# prm_405.net
KiCad netlist of a schematic drawn in EAGLE
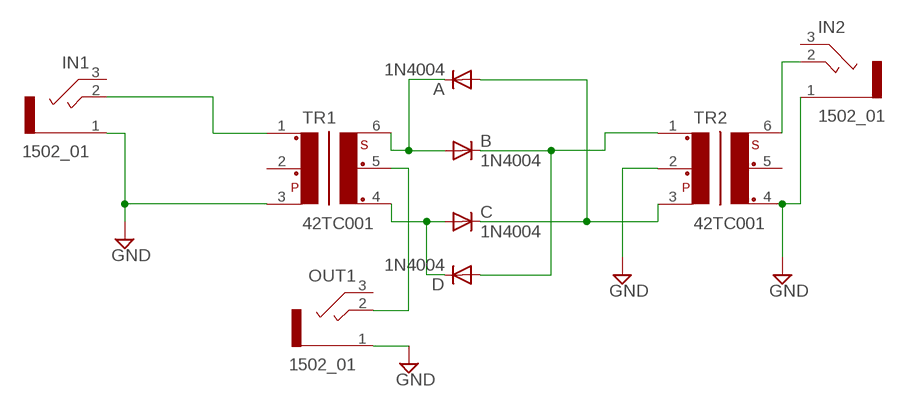
[diagram p0: schematic, sheet 1]

(export (version "E")
  (design (tool "Eeschema 10.0.6"))
  (components
    (comp (ref "A")
      (value "1N4004")
      (footprint "eagle-import:DO41-10")
      (libsource (lib "eagle-import") (part "1N4004"))
    )
    (comp (ref "B")
      (value "1N4004")
      (footprint "eagle-import:DO41-10")
      (libsource (lib "eagle-import") (part "1N4004"))
    )
    (comp (ref "C")
      (value "1N4004")
      (footprint "eagle-import:DO41-10")
      (libsource (lib "eagle-import") (part "1N4004"))
    )
    (comp (ref "D")
      (value "1N4004")
      (footprint "eagle-import:DO41-10")
      (libsource (lib "eagle-import") (part "1N4004"))
    )
    (comp (ref "IN1")
      (value "1502_01")
      (footprint "eagle-import:1502_01")
      (libsource (lib "eagle-import") (part "1502_01"))
    )
    (comp (ref "IN2")
      (value "1502_01")
      (footprint "eagle-import:1502_01")
      (libsource (lib "eagle-import") (part "1502_01"))
    )
    (comp (ref "OUT1")
      (value "1502_01")
      (footprint "eagle-import:1502_01")
      (libsource (lib "eagle-import") (part "1502_01"))
    )
    (comp (ref "TR1")
      (value "42TC001")
      (footprint "eagle-import:42TC")
      (libsource (lib "eagle-import") (part "42T?C001"))
    )
    (comp (ref "TR2")
      (value "42TC001")
      (footprint "eagle-import:42TC")
      (libsource (lib "eagle-import") (part "42T?C001"))
    )
  )
  (nets
    (net (code "1") (name "GND") (class "Default")
      (node (ref "IN1") (pin "1") (pinfunction "1_1") (pintype "passive"))
      (node (ref "IN2") (pin "1") (pinfunction "1_1") (pintype "passive"))
      (node (ref "OUT1") (pin "1") (pinfunction "1_1") (pintype "passive"))
      (node (ref "TR1") (pin "3") (pinfunction "3_3") (pintype "passive"))
      (node (ref "TR2") (pin "2") (pinfunction "2_2") (pintype "passive"))
      (node (ref "TR2") (pin "4") (pinfunction "4_4") (pintype "passive"))
    )
    (net (code "2") (name "Net-(A-PadA)") (class "Default")
      (node (ref "A") (pin "A") (pinfunction "A_A") (pintype "passive"))
      (node (ref "C") (pin "C") (pinfunction "C_C") (pintype "passive"))
      (node (ref "TR2") (pin "3") (pinfunction "3_3") (pintype "passive"))
    )
    (net (code "3") (name "Net-(A-PadC)") (class "Default")
      (node (ref "A") (pin "C") (pinfunction "C_C") (pintype "passive"))
      (node (ref "B") (pin "A") (pinfunction "A_A") (pintype "passive"))
      (node (ref "TR1") (pin "6") (pinfunction "6_6") (pintype "passive"))
    )
    (net (code "4") (name "Net-(B-PadC)") (class "Default")
      (node (ref "B") (pin "C") (pinfunction "C_C") (pintype "passive"))
      (node (ref "D") (pin "A") (pinfunction "A_A") (pintype "passive"))
      (node (ref "TR2") (pin "1") (pinfunction "1_1") (pintype "passive"))
    )
    (net (code "5") (name "Net-(C-PadA)") (class "Default")
      (node (ref "C") (pin "A") (pinfunction "A_A") (pintype "passive"))
      (node (ref "D") (pin "C") (pinfunction "C_C") (pintype "passive"))
      (node (ref "TR1") (pin "4") (pinfunction "4_4") (pintype "passive"))
    )
    (net (code "6") (name "Net-(IN1-3)") (class "Default")
      (node (ref "IN1") (pin "2") (pinfunction "3_2") (pintype "passive"))
      (node (ref "TR1") (pin "1") (pinfunction "1_1") (pintype "passive"))
    )
    (net (code "7") (name "Net-(IN2-3)") (class "Default")
      (node (ref "IN2") (pin "2") (pinfunction "3_2") (pintype "passive"))
      (node (ref "TR2") (pin "6") (pinfunction "6_6") (pintype "passive"))
    )
    (net (code "8") (name "Net-(OUT1-3)") (class "Default")
      (node (ref "OUT1") (pin "2") (pinfunction "3_2") (pintype "passive"))
      (node (ref "TR1") (pin "5") (pinfunction "5_5") (pintype "passive"))
    )
    (net (code "9") (name "unconnected-(IN1-2-Pad3)") (class "Default")
      (node (ref "IN1") (pin "3") (pinfunction "2_3") (pintype "passive"))
    )
    (net (code "10") (name "unconnected-(IN2-2-Pad3)") (class "Default")
      (node (ref "IN2") (pin "3") (pinfunction "2_3") (pintype "passive"))
    )
    (net (code "11") (name "unconnected-(OUT1-2-Pad3)") (class "Default")
      (node (ref "OUT1") (pin "3") (pinfunction "2_3") (pintype "passive"))
    )
    (net (code "12") (name "unconnected-(TR1-Pad2)") (class "Default")
      (node (ref "TR1") (pin "2") (pinfunction "2_2") (pintype "passive"))
    )
    (net (code "13") (name "unconnected-(TR2-Pad5)") (class "Default")
      (node (ref "TR2") (pin "5") (pinfunction "5_5") (pintype "passive"))
    )
  )
)
